# version1.net
KiCad netlist of a schematic drawn in EAGLE
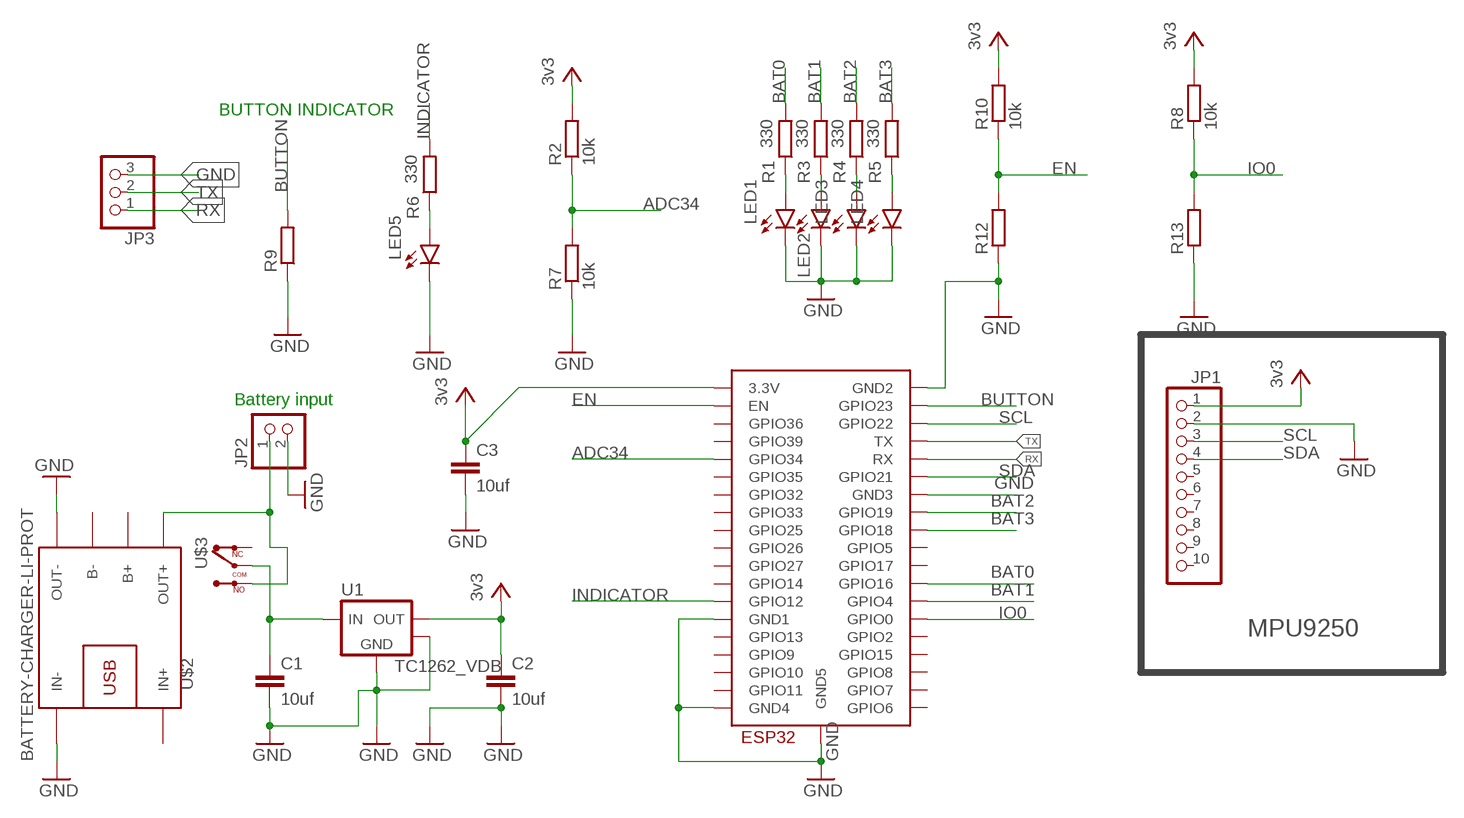
[diagram p0: schematic, sheet 1]

(export (version "E")
  (design (tool "Eeschema 10.0.6"))
  (components
    (comp (ref "C1")
      (value "10uf")
      (footprint "eagle-import:C0805")
      (libsource (lib "eagle-import") (part "C-EUC0805"))
    )
    (comp (ref "C2")
      (value "10uf")
      (footprint "eagle-import:C0805")
      (libsource (lib "eagle-import") (part "C-EUC0805"))
    )
    (comp (ref "C3")
      (value "10uf")
      (footprint "eagle-import:C0805")
      (libsource (lib "eagle-import") (part "C-EUC0805"))
    )
    (comp (ref "JP1")
      (value "PINHD-1X10_2.54-SMD-90°")
      (footprint "eagle-import:1X10SMD_90")
      (libsource (lib "eagle-import") (part "PINHD-1X10_2.54-SMD-90°"))
    )
    (comp (ref "JP2")
      (value "PINHD-1X2")
      (footprint "eagle-import:1X02")
      (libsource (lib "eagle-import") (part "PINHD-1X2"))
    )
    (comp (ref "JP3")
      (value "PINHD-1X3")
      (footprint "eagle-import:1X03")
      (libsource (lib "eagle-import") (part "PINHD-1X3"))
    )
    (comp (ref "LED1")
      (value "LEDSML0805")
      (footprint "eagle-import:SML0805")
      (libsource (lib "eagle-import") (part "LEDSML0805"))
    )
    (comp (ref "LED2")
      (value "LEDSML0805")
      (footprint "eagle-import:SML0805")
      (libsource (lib "eagle-import") (part "LEDSML0805"))
    )
    (comp (ref "LED3")
      (value "LEDSML0805")
      (footprint "eagle-import:SML0805")
      (libsource (lib "eagle-import") (part "LEDSML0805"))
    )
    (comp (ref "LED4")
      (value "LEDSML0805")
      (footprint "eagle-import:SML0805")
      (libsource (lib "eagle-import") (part "LEDSML0805"))
    )
    (comp (ref "LED5")
      (value "LEDSML0805")
      (footprint "eagle-import:SML0805")
      (libsource (lib "eagle-import") (part "LEDSML0805"))
    )
    (comp (ref "R1")
      (value "330")
      (footprint "eagle-import:R0805")
      (libsource (lib "eagle-import") (part "R-EU_R0805"))
    )
    (comp (ref "R2")
      (value "10k")
      (footprint "eagle-import:R0805")
      (libsource (lib "eagle-import") (part "R-EU_R0805"))
    )
    (comp (ref "R3")
      (value "330")
      (footprint "eagle-import:R0805")
      (libsource (lib "eagle-import") (part "R-EU_R0805"))
    )
    (comp (ref "R4")
      (value "330")
      (footprint "eagle-import:R0805")
      (libsource (lib "eagle-import") (part "R-EU_R0805"))
    )
    (comp (ref "R5")
      (value "330")
      (footprint "eagle-import:R0805")
      (libsource (lib "eagle-import") (part "R-EU_R0805"))
    )
    (comp (ref "R6")
      (value "330")
      (footprint "eagle-import:R0805")
      (libsource (lib "eagle-import") (part "R-EU_R0805"))
    )
    (comp (ref "R7")
      (value "10k")
      (footprint "eagle-import:R0805")
      (libsource (lib "eagle-import") (part "R-EU_R0805"))
    )
    (comp (ref "R8")
      (value "10k")
      (footprint "eagle-import:R0805")
      (libsource (lib "eagle-import") (part "R-EU_R0805"))
    )
    (comp (ref "R9")
      (value "R-EU_M2309")
      (footprint "eagle-import:M2309")
      (libsource (lib "eagle-import") (part "R-EU_M2309"))
    )
    (comp (ref "R10")
      (value "10k")
      (footprint "eagle-import:R0805")
      (libsource (lib "eagle-import") (part "R-EU_R0805"))
    )
    (comp (ref "R12")
      (value "R-EU_M2309")
      (footprint "eagle-import:M2309")
      (libsource (lib "eagle-import") (part "R-EU_M2309"))
    )
    (comp (ref "R13")
      (value "R-EU_M2309")
      (footprint "eagle-import:M2309")
      (libsource (lib "eagle-import") (part "R-EU_M2309"))
    )
    (comp (ref "U$1")
      (value "ESP32-WROOM")
      (footprint "eagle-import:ESP32-WROOM")
      (libsource (lib "eagle-import") (part "ESP32-WROOM"))
    )
    (comp (ref "U$2")
      (value "BATTERY-CHARGER-LI-PROT")
      (footprint "eagle-import:BATTERY-CHARGER-LI-PROT")
      (libsource (lib "eagle-import") (part "BATTERY-CHARGER-LI-PROT"))
    )
    (comp (ref "U$3")
      (value "-MICROSW")
      (footprint "eagle-import:CON3")
      (libsource (lib "eagle-import") (part "-MICROSW"))
    )
    (comp (ref "U1")
      (value "TC1262_VDB")
      (footprint "eagle-import:SOT-223-3")
      (libsource (lib "eagle-import") (part "TC1262_VDB"))
    )
  )
  (nets
    (net (code "1") (name "/ADC34") (class "Default")
      (node (ref "R2") (pin "1") (pinfunction "1_1") (pintype "passive"))
      (node (ref "R7") (pin "2") (pinfunction "2_2") (pintype "passive"))
      (node (ref "U$1") (pin "IO34") (pinfunction "GPIO34_IO34") (pintype "bidirectional"))
    )
    (net (code "2") (name "/BAT0") (class "Default")
      (node (ref "R1") (pin "2") (pinfunction "2_2") (pintype "passive"))
      (node (ref "U$1") (pin "IO16") (pinfunction "GPIO16_IO16") (pintype "bidirectional"))
    )
    (net (code "3") (name "/BAT1") (class "Default")
      (node (ref "R3") (pin "2") (pinfunction "2_2") (pintype "passive"))
      (node (ref "U$1") (pin "IO4") (pinfunction "GPIO4_IO4") (pintype "bidirectional"))
    )
    (net (code "4") (name "/BAT2") (class "Default")
      (node (ref "R4") (pin "2") (pinfunction "2_2") (pintype "passive"))
      (node (ref "U$1") (pin "IO19") (pinfunction "GPIO19_IO19") (pintype "bidirectional"))
    )
    (net (code "5") (name "/BAT3") (class "Default")
      (node (ref "R5") (pin "2") (pinfunction "2_2") (pintype "passive"))
      (node (ref "U$1") (pin "IO18") (pinfunction "GPIO18_IO18") (pintype "bidirectional"))
    )
    (net (code "6") (name "/BUTTON") (class "Default")
      (node (ref "R9") (pin "2") (pinfunction "2_2") (pintype "passive"))
      (node (ref "U$1") (pin "IO23") (pinfunction "GPIO23_IO23") (pintype "bidirectional"))
    )
    (net (code "7") (name "/EN") (class "Default")
      (node (ref "R10") (pin "1") (pinfunction "1_1") (pintype "passive"))
      (node (ref "R12") (pin "2") (pinfunction "2_2") (pintype "passive"))
      (node (ref "U$1") (pin "EN") (pinfunction "EN_EN") (pintype "bidirectional"))
    )
    (net (code "8") (name "/INDICATOR") (class "Default")
      (node (ref "R6") (pin "2") (pinfunction "2_2") (pintype "passive"))
      (node (ref "U$1") (pin "IO12") (pinfunction "GPIO12_IO12") (pintype "bidirectional"))
    )
    (net (code "9") (name "/IO0") (class "Default")
      (node (ref "R13") (pin "2") (pinfunction "2_2") (pintype "passive"))
      (node (ref "R8") (pin "1") (pinfunction "1_1") (pintype "passive"))
      (node (ref "U$1") (pin "IO0") (pinfunction "GPIO0_IO0") (pintype "bidirectional"))
    )
    (net (code "10") (name "/SCL") (class "Default")
      (node (ref "JP1") (pin "3") (pinfunction "3_3") (pintype "passive"))
      (node (ref "U$1") (pin "IO22") (pinfunction "GPIO22_IO22") (pintype "bidirectional"))
    )
    (net (code "11") (name "/SDA") (class "Default")
      (node (ref "JP1") (pin "4") (pinfunction "4_4") (pintype "passive"))
      (node (ref "U$1") (pin "IO21") (pinfunction "GPIO21_IO21") (pintype "bidirectional"))
    )
    (net (code "12") (name "3v3") (class "Default")
      (node (ref "C2") (pin "1") (pinfunction "1_1") (pintype "passive"))
      (node (ref "C3") (pin "1") (pinfunction "1_1") (pintype "passive"))
      (node (ref "JP1") (pin "1") (pinfunction "1_1") (pintype "passive"))
      (node (ref "R10") (pin "2") (pinfunction "2_2") (pintype "passive"))
      (node (ref "R2") (pin "2") (pinfunction "2_2") (pintype "passive"))
      (node (ref "R8") (pin "2") (pinfunction "2_2") (pintype "passive"))
      (node (ref "U$1") (pin "3V3") (pinfunction "3.3V_3V3") (pintype "bidirectional"))
      (node (ref "U1") (pin "3") (pinfunction "VOUT_3") (pintype "power_in"))
    )
    (net (code "13") (name "GND") (class "Default")
      (node (ref "C1") (pin "2") (pinfunction "2_2") (pintype "passive"))
      (node (ref "C2") (pin "2") (pinfunction "2_2") (pintype "passive"))
      (node (ref "C3") (pin "2") (pinfunction "2_2") (pintype "passive"))
      (node (ref "JP1") (pin "2") (pinfunction "2_2") (pintype "passive"))
      (node (ref "JP2") (pin "2") (pinfunction "2_2") (pintype "passive"))
      (node (ref "JP3") (pin "3") (pinfunction "3_3") (pintype "passive"))
      (node (ref "LED1") (pin "C") (pinfunction "C_C") (pintype "passive"))
      (node (ref "LED2") (pin "C") (pinfunction "C_C") (pintype "passive"))
      (node (ref "LED3") (pin "C") (pinfunction "C_C") (pintype "passive"))
      (node (ref "LED4") (pin "C") (pinfunction "C_C") (pintype "passive"))
      (node (ref "LED5") (pin "C") (pinfunction "C_C") (pintype "passive"))
      (node (ref "R12") (pin "1") (pinfunction "1_1") (pintype "passive"))
      (node (ref "R13") (pin "1") (pinfunction "1_1") (pintype "passive"))
      (node (ref "R7") (pin "1") (pinfunction "1_1") (pintype "passive"))
      (node (ref "R9") (pin "1") (pinfunction "1_1") (pintype "passive"))
      (node (ref "U$1") (pin "GND1") (pinfunction "GND1_GND1") (pintype "bidirectional"))
      (node (ref "U$1") (pin "GND2") (pinfunction "GND2_GND2") (pintype "bidirectional"))
      (node (ref "U$1") (pin "GND3") (pinfunction "GND3_GND3") (pintype "bidirectional"))
      (node (ref "U$1") (pin "GND4") (pinfunction "GND4_GND4") (pintype "bidirectional"))
      (node (ref "U$1") (pin "GND5") (pinfunction "GND5_GND5") (pintype "bidirectional"))
      (node (ref "U$2") (pin "IN-") (pinfunction "IN-_IN-") (pintype "bidirectional"))
      (node (ref "U$2") (pin "OUT-") (pinfunction "OUT-_OUT-") (pintype "bidirectional"))
      (node (ref "U1") (pin "2") (pinfunction "GND_2") (pintype "power_in"))
      (node (ref "U1") (pin "4") (pinfunction "TAB_4") (pintype "power_in"))
    )
    (net (code "14") (name "Net-(JP2-Pad1)") (class "Default")
      (node (ref "JP2") (pin "1") (pinfunction "1_1") (pintype "passive"))
      (node (ref "U$2") (pin "OUT+") (pinfunction "OUT+_OUT+") (pintype "bidirectional"))
      (node (ref "U$3") (pin "P$1") (pinfunction "P$1_P$1") (pintype "passive"))
    )
    (net (code "15") (name "Net-(LED1-PadA)") (class "Default")
      (node (ref "LED1") (pin "A") (pinfunction "A_A") (pintype "passive"))
      (node (ref "R1") (pin "1") (pinfunction "1_1") (pintype "passive"))
    )
    (net (code "16") (name "Net-(LED2-PadA)") (class "Default")
      (node (ref "LED2") (pin "A") (pinfunction "A_A") (pintype "passive"))
      (node (ref "R3") (pin "1") (pinfunction "1_1") (pintype "passive"))
    )
    (net (code "17") (name "Net-(LED3-PadA)") (class "Default")
      (node (ref "LED3") (pin "A") (pinfunction "A_A") (pintype "passive"))
      (node (ref "R4") (pin "1") (pinfunction "1_1") (pintype "passive"))
    )
    (net (code "18") (name "Net-(LED4-PadA)") (class "Default")
      (node (ref "LED4") (pin "A") (pinfunction "A_A") (pintype "passive"))
      (node (ref "R5") (pin "1") (pinfunction "1_1") (pintype "passive"))
    )
    (net (code "19") (name "Net-(LED5-PadA)") (class "Default")
      (node (ref "LED5") (pin "A") (pinfunction "A_A") (pintype "passive"))
      (node (ref "R6") (pin "1") (pinfunction "1_1") (pintype "passive"))
    )
    (net (code "20") (name "Net-(U1-VIN)") (class "Default")
      (node (ref "C1") (pin "1") (pinfunction "1_1") (pintype "passive"))
      (node (ref "U$3") (pin "P$2") (pinfunction "P$2_P$2") (pintype "passive"))
      (node (ref "U1") (pin "1") (pinfunction "VIN_1") (pintype "power_in"))
    )
    (net (code "21") (name "RX") (class "Default")
      (node (ref "JP3") (pin "1") (pinfunction "1_1") (pintype "passive"))
      (node (ref "U$1") (pin "RX") (pinfunction "RX_RX") (pintype "bidirectional"))
    )
    (net (code "22") (name "TX") (class "Default")
      (node (ref "JP3") (pin "2") (pinfunction "2_2") (pintype "passive"))
      (node (ref "U$1") (pin "TX") (pinfunction "TX_TX") (pintype "bidirectional"))
    )
    (net (code "23") (name "unconnected-(JP1-Pad5)") (class "Default")
      (node (ref "JP1") (pin "5") (pinfunction "5_5") (pintype "passive"))
    )
    (net (code "24") (name "unconnected-(JP1-Pad6)") (class "Default")
      (node (ref "JP1") (pin "6") (pinfunction "6_6") (pintype "passive"))
    )
    (net (code "25") (name "unconnected-(JP1-Pad7)") (class "Default")
      (node (ref "JP1") (pin "7") (pinfunction "7_7") (pintype "passive"))
    )
    (net (code "26") (name "unconnected-(JP1-Pad8)") (class "Default")
      (node (ref "JP1") (pin "8") (pinfunction "8_8") (pintype "passive"))
    )
    (net (code "27") (name "unconnected-(JP1-Pad9)") (class "Default")
      (node (ref "JP1") (pin "9") (pinfunction "9_9") (pintype "passive"))
    )
    (net (code "28") (name "unconnected-(JP1-Pad10)") (class "Default")
      (node (ref "JP1") (pin "10") (pinfunction "10_10") (pintype "passive"))
    )
    (net (code "29") (name "unconnected-(U$1-GPIO2-PadIO2)") (class "Default")
      (node (ref "U$1") (pin "IO2") (pinfunction "GPIO2_IO2") (pintype "bidirectional"))
    )
    (net (code "30") (name "unconnected-(U$1-GPIO5-PadIO5)") (class "Default")
      (node (ref "U$1") (pin "IO5") (pinfunction "GPIO5_IO5") (pintype "bidirectional"))
    )
    (net (code "31") (name "unconnected-(U$1-GPIO6-PadCLK)") (class "Default")
      (node (ref "U$1") (pin "CLK") (pinfunction "GPIO6_CLK") (pintype "bidirectional"))
    )
    (net (code "32") (name "unconnected-(U$1-GPIO7-PadSD0)") (class "Default")
      (node (ref "U$1") (pin "SD0") (pinfunction "GPIO7_SD0") (pintype "bidirectional"))
    )
    (net (code "33") (name "unconnected-(U$1-GPIO8-PadSD1)") (class "Default")
      (node (ref "U$1") (pin "SD1") (pinfunction "GPIO8_SD1") (pintype "bidirectional"))
    )
    (net (code "34") (name "unconnected-(U$1-GPIO9-PadSD2)") (class "Default")
      (node (ref "U$1") (pin "SD2") (pinfunction "GPIO9_SD2") (pintype "bidirectional"))
    )
    (net (code "35") (name "unconnected-(U$1-GPIO10-PadSD3)") (class "Default")
      (node (ref "U$1") (pin "SD3") (pinfunction "GPIO10_SD3") (pintype "bidirectional"))
    )
    (net (code "36") (name "unconnected-(U$1-GPIO11-PadCMD)") (class "Default")
      (node (ref "U$1") (pin "CMD") (pinfunction "GPIO11_CMD") (pintype "bidirectional"))
    )
    (net (code "37") (name "unconnected-(U$1-GPIO13-PadIO13)") (class "Default")
      (node (ref "U$1") (pin "IO13") (pinfunction "GPIO13_IO13") (pintype "bidirectional"))
    )
    (net (code "38") (name "unconnected-(U$1-GPIO14-PadIO14)") (class "Default")
      (node (ref "U$1") (pin "IO14") (pinfunction "GPIO14_IO14") (pintype "bidirectional"))
    )
    (net (code "39") (name "unconnected-(U$1-GPIO15-PadIO15)") (class "Default")
      (node (ref "U$1") (pin "IO15") (pinfunction "GPIO15_IO15") (pintype "bidirectional"))
    )
    (net (code "40") (name "unconnected-(U$1-GPIO17-PadIO17)") (class "Default")
      (node (ref "U$1") (pin "IO17") (pinfunction "GPIO17_IO17") (pintype "bidirectional"))
    )
    (net (code "41") (name "unconnected-(U$1-GPIO25-PadIO25)") (class "Default")
      (node (ref "U$1") (pin "IO25") (pinfunction "GPIO25_IO25") (pintype "bidirectional"))
    )
    (net (code "42") (name "unconnected-(U$1-GPIO26-PadIO26)") (class "Default")
      (node (ref "U$1") (pin "IO26") (pinfunction "GPIO26_IO26") (pintype "bidirectional"))
    )
    (net (code "43") (name "unconnected-(U$1-GPIO27-PadIO27)") (class "Default")
      (node (ref "U$1") (pin "IO27") (pinfunction "GPIO27_IO27") (pintype "bidirectional"))
    )
    (net (code "44") (name "unconnected-(U$1-GPIO32-PadIO32)") (class "Default")
      (node (ref "U$1") (pin "IO32") (pinfunction "GPIO32_IO32") (pintype "bidirectional"))
    )
    (net (code "45") (name "unconnected-(U$1-GPIO33-PadIO33)") (class "Default")
      (node (ref "U$1") (pin "IO33") (pinfunction "GPIO33_IO33") (pintype "bidirectional"))
    )
    (net (code "46") (name "unconnected-(U$1-GPIO35-PadIO35)") (class "Default")
      (node (ref "U$1") (pin "IO35") (pinfunction "GPIO35_IO35") (pintype "bidirectional"))
    )
    (net (code "47") (name "unconnected-(U$1-GPIO36-PadSENSOR_VP)") (class "Default")
      (node (ref "U$1") (pin "SENSOR_VP") (pinfunction "GPIO36_SENSOR_VP") (pintype "bidirectional"))
    )
    (net (code "48") (name "unconnected-(U$1-GPIO39-PadSENSOR_VN)") (class "Default")
      (node (ref "U$1") (pin "SENSOR_VN") (pinfunction "GPIO39_SENSOR_VN") (pintype "bidirectional"))
    )
    (net (code "49") (name "unconnected-(U$2-PadB+)") (class "Default")
      (node (ref "U$2") (pin "B+") (pinfunction "B+_B+") (pintype "bidirectional"))
    )
    (net (code "50") (name "unconnected-(U$2-PadB-)") (class "Default")
      (node (ref "U$2") (pin "B-") (pinfunction "B-_B-") (pintype "bidirectional"))
    )
    (net (code "51") (name "unconnected-(U$2-PadIN+)") (class "Default")
      (node (ref "U$2") (pin "IN+") (pinfunction "IN+_IN+") (pintype "bidirectional"))
    )
    (net (code "52") (name "unconnected-(U$3-PadP$3)") (class "Default")
      (node (ref "U$3") (pin "P$3") (pinfunction "P$3_P$3") (pintype "passive"))
    )
  )
)
